# Current_Measurement.net
KiCad netlist of a schematic drawn in Altium Designer
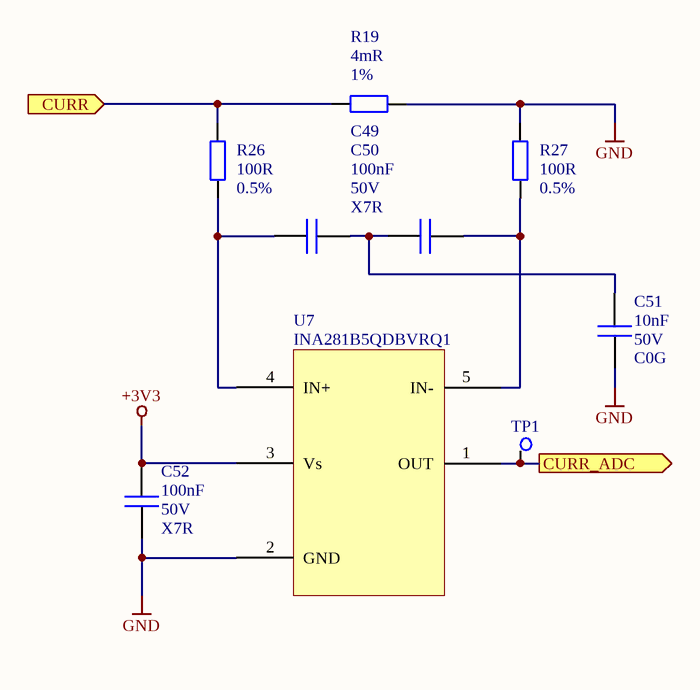
[diagram p0: Current_Measurement.SchDoc]

(export (version "E")
  (design (tool "Eeschema 10.0.6"))
  (components
    (comp (ref "C49")
      (value "100nF")
      (footprint "C_0603")
      (description "Capacitor")
      (fields
        (field (name "VOLTAGE") "50V")
        (field (name "DIELECTRIC") "X7R")
        (field (name "PART NUMBER") "C_100nF_50V_0603")
        (field (name "MANUFACTURER") "Kemet")
      )
      (libsource (lib "ProgresjaSpace") (part "C"))
    )
    (comp (ref "C50")
      (value "C")
      (footprint "C_0603")
      (description "Capacitor")
      (fields (field (name "VOLTAGE") "50V") (field (name "PART NUMBER") "C_100nF_50V_0603"))
      (libsource (lib "ProgresjaSpace") (part "C"))
    )
    (comp (ref "C51")
      (value "10nF")
      (footprint "C_0603")
      (description "Capacitor")
      (fields
        (field (name "VOLTAGE") "50V")
        (field (name "DIELECTRIC") "C0G")
        (field (name "PART NUMBER") "C_10nF_50V_0603")
        (field (name "MANUFACTURER") "Kemet")
      )
      (libsource (lib "ProgresjaSpace") (part "C"))
    )
    (comp (ref "C52")
      (value "100nF")
      (footprint "C_0603")
      (description "Capacitor")
      (fields
        (field (name "VOLTAGE") "50V")
        (field (name "DIELECTRIC") "X7R")
        (field (name "PART NUMBER") "C_100nF_50V_0603")
        (field (name "MANUFACTURER") "Kemet")
      )
      (libsource (lib "ProgresjaSpace") (part "C"))
    )
    (comp (ref "R19")
      (value "4mR")
      (footprint "R_1206")
      (fields
        (field (name "TOLERANCE") "1%")
        (field (name "PART NUMBER") "R_4mR_NA_1206")
        (field (name "VOLTAGE") "NA")
        (field (name "MANUFACTURER") "YAGEO")
      )
      (libsource (lib "") (part "R_1"))
    )
    (comp (ref "R26")
      (value "100R")
      (footprint "R_0402")
      (fields
        (field (name "TOLERANCE") "0.5%")
        (field (name "PART NUMBER") "R_100R_50V_0402")
        (field (name "VOLTAGE") "50V")
        (field (name "MANUFACTURER") "Vishay")
      )
      (libsource (lib "ProgresjaSpace") (part "R"))
    )
    (comp (ref "R27")
      (value "100R")
      (footprint "R_0402")
      (fields
        (field (name "TOLERANCE") "0.5%")
        (field (name "PART NUMBER") "R_100R_50V_0402")
        (field (name "VOLTAGE") "50V")
        (field (name "MANUFACTURER") "Vishay")
      )
      (libsource (lib "ProgresjaSpace") (part "R"))
    )
    (comp (ref "TP1")
      (value "TP_TestPoint")
      (footprint "TP_01")
      (fields (field (name "PART NUMBER") "TestPoint1") (field (name "MANUFACTURER") "Progresja Space"))
      (libsource (lib "ProgresjaSpace") (part "TP_TestPoint"))
    )
    (comp (ref "U7")
      (value "INA281B5QDBVRQ1")
      (footprint "SOT_23_5")
      (description "Current Sense Amplifiers Automotive AEC-Q100, -4-V to 110-V, 1.3-MHz")
      (fields (field (name "MANUFACTURER") "TI") (field (name "Comment") "IC_INA281B_Q1"))
      (libsource (lib "ProgresjaSpace") (part "IC_INA281B_Q1"))
    )
  )
  (nets
    (net (code "1") (name "+3V3") (class "Default")
      (node (ref "C52") (pin "1") (pinfunction "1_1") (pintype "passive"))
      (node (ref "U7") (pin "3") (pinfunction "Vs_3") (pintype "passive"))
    )
    (net (code "2") (name "/CURR") (class "Default")
      (node (ref "R19") (pin "1") (pinfunction "1_1") (pintype "passive"))
      (node (ref "R26") (pin "1") (pinfunction "1_1") (pintype "passive"))
    )
    (net (code "3") (name "/CURR_ADC") (class "Default")
      (node (ref "TP1") (pin "1") (pinfunction "1_1") (pintype "passive"))
      (node (ref "U7") (pin "1") (pinfunction "OUT_1") (pintype "passive"))
    )
    (net (code "4") (name "GND") (class "Default")
      (node (ref "C51") (pin "2") (pinfunction "2_2") (pintype "passive"))
      (node (ref "C52") (pin "2") (pinfunction "2_2") (pintype "passive"))
      (node (ref "R19") (pin "2") (pinfunction "2_2") (pintype "passive"))
      (node (ref "R27") (pin "1") (pinfunction "1_1") (pintype "passive"))
      (node (ref "U7") (pin "2") (pinfunction "GND_2") (pintype "passive"))
    )
    (net (code "5") (name "Net-(C49-Pad2)") (class "Default")
      (node (ref "C49") (pin "2") (pinfunction "2_2") (pintype "passive"))
      (node (ref "C50") (pin "1") (pinfunction "1_1") (pintype "passive"))
      (node (ref "C51") (pin "1") (pinfunction "1_1") (pintype "passive"))
    )
    (net (code "6") (name "Net-(U7-IN+)") (class "Default")
      (node (ref "C49") (pin "1") (pinfunction "1_1") (pintype "passive"))
      (node (ref "R26") (pin "2") (pinfunction "2_2") (pintype "passive"))
      (node (ref "U7") (pin "4") (pinfunction "IN+_4") (pintype "passive"))
    )
    (net (code "7") (name "Net-(U7-IN-)") (class "Default")
      (node (ref "C50") (pin "2") (pinfunction "2_2") (pintype "passive"))
      (node (ref "R27") (pin "2") (pinfunction "2_2") (pintype "passive"))
      (node (ref "U7") (pin "5") (pinfunction "IN-_5") (pintype "passive"))
    )
  )
)
